# ADT7302.net
KiCad netlist of a schematic drawn in EAGLE
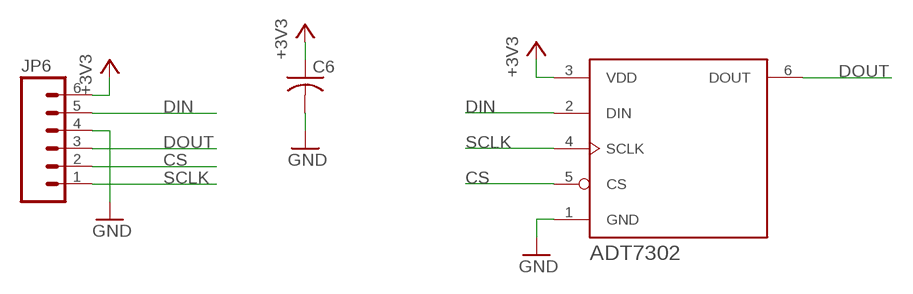
[diagram p0: schematic, sheet 1]

(export (version "E")
  (design (tool "Eeschema 10.0.6"))
  (components
    (comp (ref "C6")
      (value "C-USC0805K")
      (footprint "eagle-import:C0805K")
      (libsource (lib "eagle-import") (part "C-USC0805K"))
    )
    (comp (ref "JP6")
      (value "M06LOCK")
      (footprint "eagle-import:1X06_LOCK")
      (libsource (lib "eagle-import") (part "M06LOCK"))
    )
    (comp (ref "U$2")
      (value "ADT7302")
      (footprint "eagle-import:SOT23")
      (libsource (lib "eagle-import") (part "ADT7302"))
    )
  )
  (nets
    (net (code "1") (name "+3V3") (class "Default")
      (node (ref "C6") (pin "1") (pinfunction "1_1") (pintype "passive"))
      (node (ref "JP6") (pin "6") (pinfunction "6_6") (pintype "passive"))
      (node (ref "U$2") (pin "3") (pinfunction "VDD_3") (pintype "power_in"))
    )
    (net (code "2") (name "/CS") (class "Default")
      (node (ref "JP6") (pin "2") (pinfunction "2_2") (pintype "passive"))
      (node (ref "U$2") (pin "5") (pinfunction "CS_5") (pintype "input"))
    )
    (net (code "3") (name "/DIN") (class "Default")
      (node (ref "JP6") (pin "5") (pinfunction "5_5") (pintype "passive"))
      (node (ref "U$2") (pin "2") (pinfunction "DIN_2") (pintype "input"))
    )
    (net (code "4") (name "/DOUT") (class "Default")
      (node (ref "JP6") (pin "3") (pinfunction "3_3") (pintype "passive"))
      (node (ref "U$2") (pin "6") (pinfunction "DOUT_6") (pintype "output"))
    )
    (net (code "5") (name "/SCLK") (class "Default")
      (node (ref "JP6") (pin "1") (pinfunction "1_1") (pintype "passive"))
      (node (ref "U$2") (pin "4") (pinfunction "SCLK_4") (pintype "input"))
    )
    (net (code "6") (name "GND") (class "Default")
      (node (ref "C6") (pin "2") (pinfunction "2_2") (pintype "passive"))
      (node (ref "JP6") (pin "4") (pinfunction "4_4") (pintype "passive"))
      (node (ref "U$2") (pin "1") (pinfunction "GND_1") (pintype "power_in"))
    )
  )
)
